# 15_ISP.net
KiCad netlist of a schematic drawn in Altium Designer
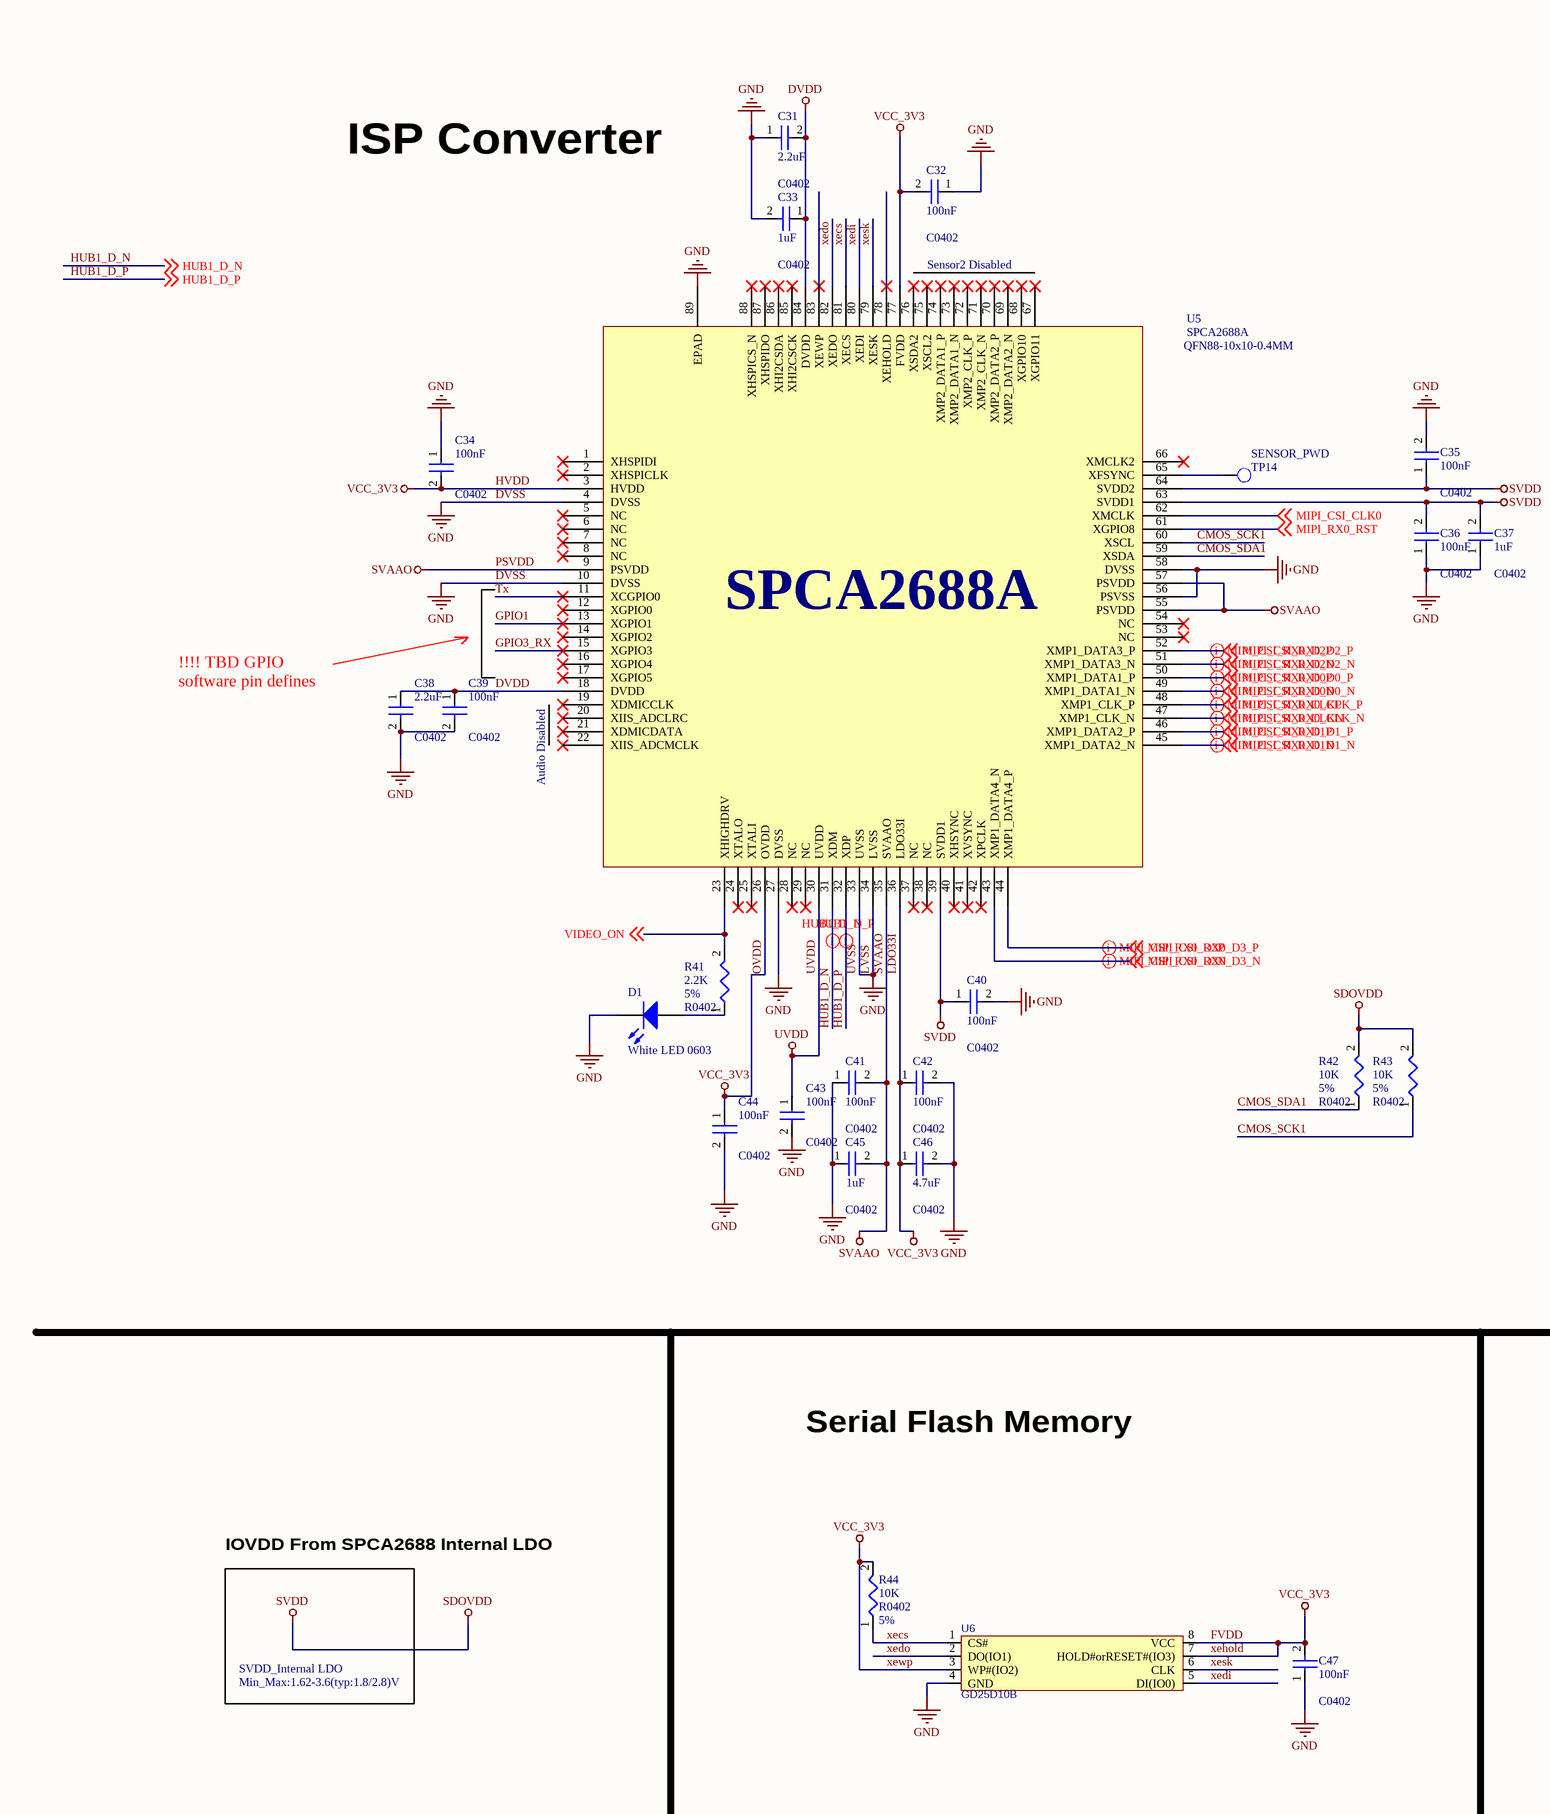
[diagram p0: 15_ISP.SchDoc, left]
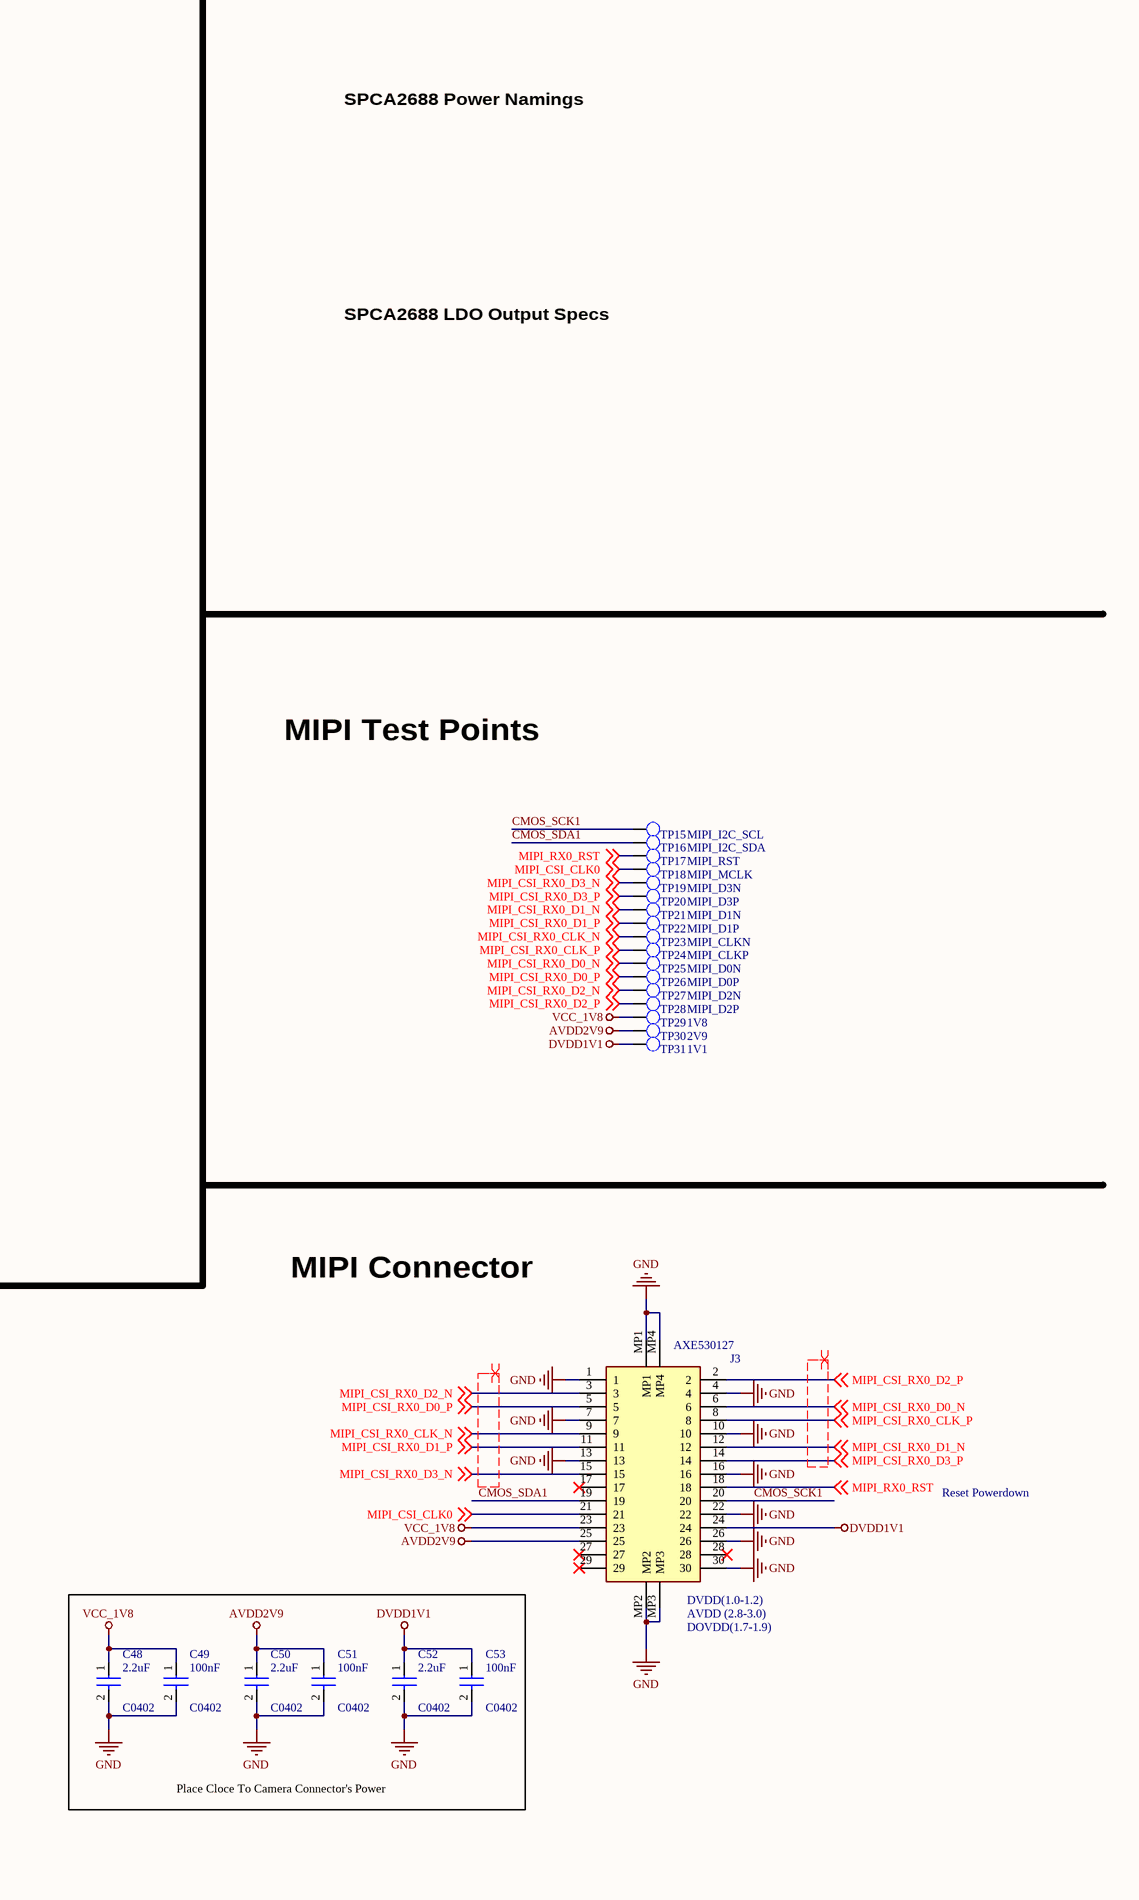
[diagram p1: 15_ISP.SchDoc, right]

(export (version "E")
  (design (tool "Eeschema 10.0.6"))
  (components
    (comp (ref "C31")
      (value "2.2uF")
      (footprint "C0402_L")
      (description "cap,2.20uF,+/-10%,10V,X5R,C0402")
      (fields (field (name "PCB FOOTPRINT") "C0402"))
      (libsource (lib "*") (part "CAP NP_Dup1"))
    )
    (comp (ref "C32")
      (value "100nF")
      (footprint "C0402_L")
      (description "cap,100.00nF,+/-10%,25V,X5R,C0402")
      (fields (field (name "PCB FOOTPRINT") "C0402"))
      (libsource (lib "*") (part "CAP NP_Dup1"))
    )
    (comp (ref "C33")
      (value "1uF")
      (footprint "C0402_L")
      (description "cap,1.00uF,+/-10%,6.3V,X5R,C0402")
      (fields (field (name "PCB FOOTPRINT") "C0402"))
      (libsource (lib "*") (part "CAP NP_Dup1"))
    )
    (comp (ref "C34")
      (value "100nF")
      (footprint "C0402_L")
      (description "cap,100.00nF,+/-10%,25V,X5R,C0402")
      (fields (field (name "PCB FOOTPRINT") "C0402"))
      (libsource (lib "*") (part "CAP NP_Dup1"))
    )
    (comp (ref "C35")
      (value "100nF")
      (footprint "C0402_L")
      (description "cap,100.00nF,+/-10%,25V,X5R,C0402")
      (fields (field (name "PCB FOOTPRINT") "C0402"))
      (libsource (lib "*") (part "CAP NP_Dup1"))
    )
    (comp (ref "C36")
      (value "100nF")
      (footprint "C0402_L")
      (description "cap,100.00nF,+/-10%,25V,X5R,C0402")
      (fields (field (name "PCB FOOTPRINT") "C0402"))
      (libsource (lib "*") (part "CAP NP_Dup1"))
    )
    (comp (ref "C37")
      (value "1uF")
      (footprint "C0402_L")
      (description "cap,1.00uF,+/-10%,6.3V,X5R,C0402")
      (fields (field (name "PCB FOOTPRINT") "C0402"))
      (libsource (lib "*") (part "CAP NP_Dup1"))
    )
    (comp (ref "C38")
      (value "2.2uF")
      (footprint "C0402_L")
      (description "cap,2.20uF,+/-10%,10V,X5R,C0402")
      (fields (field (name "PCB FOOTPRINT") "C0402"))
      (libsource (lib "*") (part "CAP NP_Dup1"))
    )
    (comp (ref "C39")
      (value "100nF")
      (footprint "C0402_L")
      (description "cap,100.00nF,+/-10%,25V,X5R,C0402")
      (fields (field (name "PCB FOOTPRINT") "C0402"))
      (libsource (lib "*") (part "CAP NP_Dup1"))
    )
    (comp (ref "C40")
      (value "100nF")
      (footprint "C0402_L")
      (description "cap,100.00nF,+/-10%,25V,X5R,C0402")
      (fields (field (name "PCB FOOTPRINT") "C0402"))
      (libsource (lib "*") (part "CAP NP_Dup1"))
    )
    (comp (ref "C41")
      (value "100nF")
      (footprint "C0402_L")
      (description "cap,100.00nF,+/-10%,25V,X5R,C0402")
      (fields (field (name "PCB FOOTPRINT") "C0402"))
      (libsource (lib "*") (part "CAP NP_Dup1"))
    )
    (comp (ref "C42")
      (value "100nF")
      (footprint "C0402_L")
      (description "cap,100.00nF,+/-10%,25V,X5R,C0402")
      (fields (field (name "PCB FOOTPRINT") "C0402"))
      (libsource (lib "*") (part "CAP NP_Dup1"))
    )
    (comp (ref "C43")
      (value "100nF")
      (footprint "C0402_L")
      (description "cap,100.00nF,+/-10%,25V,X5R,C0402")
      (fields (field (name "PCB FOOTPRINT") "C0402"))
      (libsource (lib "*") (part "CAP NP_Dup1"))
    )
    (comp (ref "C44")
      (value "100nF")
      (footprint "C0402_L")
      (description "cap,100.00nF,+/-10%,25V,X5R,C0402")
      (fields (field (name "PCB FOOTPRINT") "C0402"))
      (libsource (lib "*") (part "CAP NP_Dup1"))
    )
    (comp (ref "C45")
      (value "1uF")
      (footprint "C0402_L")
      (description "cap,1.00uF,+/-10%,10V,X5R,C0402")
      (fields (field (name "PCB FOOTPRINT") "C0402"))
      (libsource (lib "*") (part "CAP NP_Dup1"))
    )
    (comp (ref "C46")
      (value "4.7uF")
      (footprint "C0402_L")
      (description "cap,4.70uF,+/-10%,6.3V,X5R,C0402")
      (fields (field (name "PCB FOOTPRINT") "C0402"))
      (libsource (lib "*") (part "CAP NP_Dup1"))
    )
    (comp (ref "C47")
      (value "100nF")
      (footprint "C0402_L")
      (description "cap,100.00nF,+/-10%,25V,X5R,C0402")
      (fields (field (name "PCB FOOTPRINT") "C0402"))
      (libsource (lib "*") (part "CAP NP_Dup1"))
    )
    (comp (ref "C48")
      (value "2.2uF")
      (footprint "C0402_L")
      (description "cap,2.20uF,+/-10%,10V,X5R,C0402")
      (fields (field (name "PCB FOOTPRINT") "C0402"))
      (libsource (lib "*") (part "CAP NP_Dup1"))
    )
    (comp (ref "C49")
      (value "100nF")
      (footprint "C0402_L")
      (description "cap,100.00nF,+/-10%,25V,X5R,C0402")
      (fields (field (name "PCB FOOTPRINT") "C0402"))
      (libsource (lib "*") (part "CAP NP_Dup1"))
    )
    (comp (ref "C50")
      (value "2.2uF")
      (footprint "C0402_L")
      (description "cap,2.20uF,+/-10%,10V,X5R,C0402")
      (fields (field (name "PCB FOOTPRINT") "C0402"))
      (libsource (lib "*") (part "CAP NP_Dup1"))
    )
    (comp (ref "C51")
      (value "100nF")
      (footprint "C0402_L")
      (description "cap,100.00nF,+/-10%,25V,X5R,C0402")
      (fields (field (name "PCB FOOTPRINT") "C0402"))
      (libsource (lib "*") (part "CAP NP_Dup1"))
    )
    (comp (ref "C52")
      (value "2.2uF")
      (footprint "C0402_L")
      (description "cap,2.20uF,+/-10%,10V,X5R,C0402")
      (fields (field (name "PCB FOOTPRINT") "C0402"))
      (libsource (lib "*") (part "CAP NP_Dup1"))
    )
    (comp (ref "C53")
      (value "100nF")
      (footprint "C0402_L")
      (description "cap,100.00nF,+/-10%,25V,X5R,C0402")
      (fields (field (name "PCB FOOTPRINT") "C0402"))
      (libsource (lib "*") (part "CAP NP_Dup1"))
    )
    (comp (ref "D1")
      (value "White LED 0603")
      (footprint "LED0603_W")
      (description "LED 0603 Wite 发光二极管")
      (libsource (lib "0.3 - LED发光二极管-IR二极管_接收管-光耦") (part "LED"))
    )
    (comp (ref "J3")
      (value "AXE530127")
      (footprint "AXE530127_counterclock_pin")
      (description "AXE530127 Connector")
      (fields (field (name "MOUSER2 PART NUMBER") "679-AXE530127"))
      (libsource (lib "*") (part "AXE530127"))
    )
    (comp (ref "R41")
      (value "2.2K")
      (footprint "R0402")
      (description "通用厚膜电阻,2.2K,+/-5%,R0402")
      (fields (field (name "PCB FOOTPRINT") "R0402") (field (name "TOLERANCE") "5%"))
      (libsource (lib "*") (part "RESISTOR"))
    )
    (comp (ref "R42")
      (value "10K")
      (footprint "R0402")
      (description "通用厚膜电阻,10K,+/-5%,R0402")
      (fields (field (name "PCB FOOTPRINT") "R0402") (field (name "TOLERANCE") "5%"))
      (libsource (lib "*") (part "RESISTOR"))
    )
    (comp (ref "R43")
      (value "10K")
      (footprint "R0402")
      (description "通用厚膜电阻,10K,+/-5%,R0402")
      (fields (field (name "PCB FOOTPRINT") "R0402") (field (name "TOLERANCE") "5%"))
      (libsource (lib "*") (part "RESISTOR"))
    )
    (comp (ref "R44")
      (value "10K")
      (footprint "R0402")
      (description "通用厚膜电阻,10K,+/-5%,R0402")
      (fields (field (name "PCB FOOTPRINT") "R0402") (field (name "TOLERANCE") "5%"))
      (libsource (lib "*") (part "RESISTOR"))
    )
    (comp (ref "TP14")
      (value "SENSOR_PWD")
      (footprint "TP_0R70")
      (description "Test Point 0.7mm")
      (libsource (lib "Schlib1") (part "TP"))
    )
    (comp (ref "TP15")
      (value "MIPI_I2C_SCL")
      (footprint "TP_0R70")
      (description "Test Point 0.7mm")
      (libsource (lib "Schlib1") (part "TP"))
    )
    (comp (ref "TP16")
      (value "MIPI_I2C_SDA")
      (footprint "TP_0R70")
      (description "Test Point 0.7mm")
      (libsource (lib "Schlib1") (part "TP"))
    )
    (comp (ref "TP17")
      (value "MIPI_RST")
      (footprint "TP_0R70")
      (description "Test Point 0.7mm")
      (libsource (lib "Schlib1") (part "TP"))
    )
    (comp (ref "TP18")
      (value "MIPI_MCLK")
      (footprint "TP_0R70")
      (description "Test Point 0.7mm")
      (libsource (lib "Schlib1") (part "TP"))
    )
    (comp (ref "TP19")
      (value "MIPI_D3N")
      (footprint "TP_0R70")
      (description "Test Point 0.7mm")
      (libsource (lib "Schlib1") (part "TP"))
    )
    (comp (ref "TP20")
      (value "MIPI_D3P")
      (footprint "TP_0R70")
      (description "Test Point 0.7mm")
      (libsource (lib "Schlib1") (part "TP"))
    )
    (comp (ref "TP21")
      (value "MIPI_D1N")
      (footprint "TP_0R70")
      (description "Test Point 0.7mm")
      (libsource (lib "Schlib1") (part "TP"))
    )
    (comp (ref "TP22")
      (value "MIPI_D1P")
      (footprint "TP_0R70")
      (description "Test Point 0.7mm")
      (libsource (lib "Schlib1") (part "TP"))
    )
    (comp (ref "TP23")
      (value "MIPI_CLKN")
      (footprint "TP_0R70")
      (description "Test Point 0.7mm")
      (libsource (lib "Schlib1") (part "TP"))
    )
    (comp (ref "TP24")
      (value "MIPI_CLKP")
      (footprint "TP_0R70")
      (description "Test Point 0.7mm")
      (libsource (lib "Schlib1") (part "TP"))
    )
    (comp (ref "TP25")
      (value "MIPI_D0N")
      (footprint "TP_0R70")
      (description "Test Point 0.7mm")
      (libsource (lib "Schlib1") (part "TP"))
    )
    (comp (ref "TP26")
      (value "MIPI_D0P")
      (footprint "TP_0R70")
      (description "Test Point 0.7mm")
      (libsource (lib "Schlib1") (part "TP"))
    )
    (comp (ref "TP27")
      (value "MIPI_D2N")
      (footprint "TP_0R70")
      (description "Test Point 0.7mm")
      (libsource (lib "Schlib1") (part "TP"))
    )
    (comp (ref "TP28")
      (value "MIPI_D2P")
      (footprint "TP_0R70")
      (description "Test Point 0.7mm")
      (libsource (lib "Schlib1") (part "TP"))
    )
    (comp (ref "TP29")
      (value "1V8")
      (footprint "TP_0R70")
      (description "Test Point 0.7mm")
      (libsource (lib "Schlib1") (part "TP"))
    )
    (comp (ref "TP30")
      (value "2V9")
      (footprint "TP_0R70")
      (description "Test Point 0.7mm")
      (libsource (lib "Schlib1") (part "TP"))
    )
    (comp (ref "TP31")
      (value "1V1")
      (footprint "TP_0R70")
      (description "Test Point 0.7mm")
      (libsource (lib "Schlib1") (part "TP"))
    )
    (comp (ref "U5")
      (value "SPCA2688A")
      (footprint "QFN40P1000X1000X90-89N")
      (description "SPCA2688A ISP IC\r\nQFN88 10x10MM 0.4MM")
      (libsource (lib "Schlib1") (part "SPCA2688A"))
    )
    (comp (ref "U6")
      (value "GD25D10B")
      (footprint "SOIC-8")
      (description "SPI FLASH SOP-8")
      (libsource (lib "Schlib1") (part "GD25D10B"))
    )
  )
  (nets
    (net (code "1") (name "/CMOS_SCK1") (class "Default")
      (node (ref "J3") (pin "20") (pinfunction "20_20") (pintype "passive"))
      (node (ref "R43") (pin "1") (pinfunction "1_1") (pintype "passive"))
      (node (ref "TP15") (pin "1") (pinfunction "1_1") (pintype "passive"))
      (node (ref "U5") (pin "60") (pinfunction "XSCL_60") (pintype "passive"))
    )
    (net (code "2") (name "/CMOS_SDA1") (class "Default")
      (node (ref "J3") (pin "19") (pinfunction "19_19") (pintype "passive"))
      (node (ref "R42") (pin "1") (pinfunction "1_1") (pintype "passive"))
      (node (ref "TP16") (pin "1") (pinfunction "1_1") (pintype "passive"))
      (node (ref "U5") (pin "59") (pinfunction "XSDA_59") (pintype "passive"))
    )
    (net (code "3") (name "/GPIO1") (class "Default")
      (node (ref "U5") (pin "13") (pinfunction "XGPIO1_13") (pintype "passive+no_connect"))
    )
    (net (code "4") (name "/GPIO3_RX") (class "Default")
      (node (ref "U5") (pin "15") (pinfunction "XGPIO3_15") (pintype "passive+no_connect"))
    )
    (net (code "5") (name "/Tx") (class "Default")
      (node (ref "U5") (pin "11") (pinfunction "XCGPIO0_11") (pintype "passive+no_connect"))
    )
    (net (code "6") (name "/xecs") (class "Default")
      (node (ref "R44") (pin "1") (pinfunction "1_1") (pintype "passive"))
      (node (ref "U5") (pin "81") (pinfunction "XECS_81") (pintype "passive"))
      (node (ref "U6") (pin "1") (pinfunction "CS#_1") (pintype "passive"))
    )
    (net (code "7") (name "/xedi") (class "Default")
      (node (ref "U5") (pin "80") (pinfunction "XEDI_80") (pintype "passive"))
      (node (ref "U6") (pin "5") (pinfunction "DI(IO0)_5") (pintype "passive"))
    )
    (net (code "8") (name "/xedo") (class "Default")
      (node (ref "U5") (pin "82") (pinfunction "XEDO_82") (pintype "passive"))
      (node (ref "U6") (pin "2") (pinfunction "DO(IO1)_2") (pintype "passive"))
    )
    (net (code "9") (name "/xesk") (class "Default")
      (node (ref "U5") (pin "79") (pinfunction "XESK_79") (pintype "passive"))
      (node (ref "U6") (pin "6") (pinfunction "CLK_6") (pintype "passive"))
    )
    (net (code "10") (name "AVDD2V9") (class "Default")
      (node (ref "C50") (pin "1") (pinfunction "1_1") (pintype "passive"))
      (node (ref "C51") (pin "1") (pinfunction "1_1") (pintype "passive"))
      (node (ref "J3") (pin "25") (pinfunction "25_25") (pintype "passive"))
      (node (ref "TP30") (pin "1") (pinfunction "1_1") (pintype "passive"))
    )
    (net (code "11") (name "DVDD") (class "Default")
      (node (ref "C31") (pin "2") (pinfunction "2_2") (pintype "passive"))
      (node (ref "C33") (pin "1") (pinfunction "1_1") (pintype "passive"))
      (node (ref "C38") (pin "1") (pinfunction "1_1") (pintype "passive"))
      (node (ref "C39") (pin "1") (pinfunction "1_1") (pintype "passive"))
      (node (ref "U5") (pin "18") (pinfunction "DVDD_18") (pintype "passive"))
      (node (ref "U5") (pin "84") (pinfunction "DVDD_84") (pintype "passive"))
    )
    (net (code "12") (name "DVDD1V1") (class "Default")
      (node (ref "C52") (pin "1") (pinfunction "1_1") (pintype "passive"))
      (node (ref "C53") (pin "1") (pinfunction "1_1") (pintype "passive"))
      (node (ref "J3") (pin "24") (pinfunction "24_24") (pintype "passive"))
      (node (ref "TP31") (pin "1") (pinfunction "1_1") (pintype "passive"))
    )
    (net (code "13") (name "GND") (class "Default")
      (node (ref "C31") (pin "1") (pinfunction "1_1") (pintype "passive"))
      (node (ref "C32") (pin "1") (pinfunction "1_1") (pintype "passive"))
      (node (ref "C33") (pin "2") (pinfunction "2_2") (pintype "passive"))
      (node (ref "C34") (pin "1") (pinfunction "1_1") (pintype "passive"))
      (node (ref "C35") (pin "2") (pinfunction "2_2") (pintype "passive"))
      (node (ref "C36") (pin "1") (pinfunction "1_1") (pintype "passive"))
      (node (ref "C37") (pin "1") (pinfunction "1_1") (pintype "passive"))
      (node (ref "C38") (pin "2") (pinfunction "2_2") (pintype "passive"))
      (node (ref "C39") (pin "2") (pinfunction "2_2") (pintype "passive"))
      (node (ref "C40") (pin "2") (pinfunction "2_2") (pintype "passive"))
      (node (ref "C41") (pin "1") (pinfunction "1_1") (pintype "passive"))
      (node (ref "C42") (pin "2") (pinfunction "2_2") (pintype "passive"))
      (node (ref "C43") (pin "2") (pinfunction "2_2") (pintype "passive"))
      (node (ref "C44") (pin "2") (pinfunction "2_2") (pintype "passive"))
      (node (ref "C45") (pin "1") (pinfunction "1_1") (pintype "passive"))
      (node (ref "C46") (pin "2") (pinfunction "2_2") (pintype "passive"))
      (node (ref "C47") (pin "1") (pinfunction "1_1") (pintype "passive"))
      (node (ref "C48") (pin "2") (pinfunction "2_2") (pintype "passive"))
      (node (ref "C49") (pin "2") (pinfunction "2_2") (pintype "passive"))
      (node (ref "C50") (pin "2") (pinfunction "2_2") (pintype "passive"))
      (node (ref "C51") (pin "2") (pinfunction "2_2") (pintype "passive"))
      (node (ref "C52") (pin "2") (pinfunction "2_2") (pintype "passive"))
      (node (ref "C53") (pin "2") (pinfunction "2_2") (pintype "passive"))
      (node (ref "D1") (pin "2") (pinfunction "K_2") (pintype "passive"))
      (node (ref "J3") (pin "1") (pinfunction "1_1") (pintype "passive"))
      (node (ref "J3") (pin "10") (pinfunction "10_10") (pintype "passive"))
      (node (ref "J3") (pin "13") (pinfunction "13_13") (pintype "passive"))
      (node (ref "J3") (pin "16") (pinfunction "16_16") (pintype "passive"))
      (node (ref "J3") (pin "22") (pinfunction "22_22") (pintype "passive"))
      (node (ref "J3") (pin "26") (pinfunction "26_26") (pintype "passive"))
      (node (ref "J3") (pin "30") (pinfunction "30_30") (pintype "passive"))
      (node (ref "J3") (pin "4") (pinfunction "4_4") (pintype "passive"))
      (node (ref "J3") (pin "7") (pinfunction "7_7") (pintype "passive"))
      (node (ref "J3") (pin "MP1") (pinfunction "MP1_MP1") (pintype "passive"))
      (node (ref "J3") (pin "MP2") (pinfunction "MP2_MP2") (pintype "passive"))
      (node (ref "J3") (pin "MP3") (pinfunction "MP3_MP3") (pintype "passive"))
      (node (ref "J3") (pin "MP4") (pinfunction "MP4_MP4") (pintype "passive"))
      (node (ref "U5") (pin "10") (pinfunction "DVSS_10") (pintype "passive"))
      (node (ref "U5") (pin "27") (pinfunction "DVSS_27") (pintype "passive"))
      (node (ref "U5") (pin "33") (pinfunction "UVSS_33") (pintype "passive"))
      (node (ref "U5") (pin "34") (pinfunction "LVSS_34") (pintype "passive"))
      (node (ref "U5") (pin "4") (pinfunction "DVSS_4") (pintype "passive"))
      (node (ref "U5") (pin "56") (pinfunction "PSVSS_56") (pintype "passive"))
      (node (ref "U5") (pin "58") (pinfunction "DVSS_58") (pintype "passive"))
      (node (ref "U5") (pin "89") (pinfunction "EPAD_89") (pintype "passive"))
      (node (ref "U6") (pin "4") (pinfunction "GND_4") (pintype "passive"))
    )
    (net (code "14") (name "HUB1_D_N") (class "Default")
      (node (ref "U5") (pin "31") (pinfunction "XDM_31") (pintype "passive"))
    )
    (net (code "15") (name "HUB1_D_P") (class "Default")
      (node (ref "U5") (pin "32") (pinfunction "XDP_32") (pintype "passive"))
    )
    (net (code "16") (name "MIPI_CSI_CLK0") (class "Default")
      (node (ref "J3") (pin "21") (pinfunction "21_21") (pintype "passive"))
      (node (ref "TP18") (pin "1") (pinfunction "1_1") (pintype "passive"))
      (node (ref "U5") (pin "62") (pinfunction "XMCLK_62") (pintype "passive"))
    )
    (net (code "17") (name "MIPI_CSI_RX0_CLK_N") (class "Default")
      (node (ref "J3") (pin "9") (pinfunction "9_9") (pintype "passive"))
      (node (ref "TP23") (pin "1") (pinfunction "1_1") (pintype "passive"))
      (node (ref "U5") (pin "47") (pinfunction "XMP1_CLK_N_47") (pintype "passive"))
    )
    (net (code "18") (name "MIPI_CSI_RX0_CLK_P") (class "Default")
      (node (ref "J3") (pin "8") (pinfunction "8_8") (pintype "passive"))
      (node (ref "TP24") (pin "1") (pinfunction "1_1") (pintype "passive"))
      (node (ref "U5") (pin "48") (pinfunction "XMP1_CLK_P_48") (pintype "passive"))
    )
    (net (code "19") (name "MIPI_CSI_RX0_D0_N") (class "Default")
      (node (ref "J3") (pin "6") (pinfunction "6_6") (pintype "passive"))
      (node (ref "TP25") (pin "1") (pinfunction "1_1") (pintype "passive"))
      (node (ref "U5") (pin "49") (pinfunction "XMP1_DATA1_N_49") (pintype "passive"))
    )
    (net (code "20") (name "MIPI_CSI_RX0_D0_P") (class "Default")
      (node (ref "J3") (pin "5") (pinfunction "5_5") (pintype "passive"))
      (node (ref "TP26") (pin "1") (pinfunction "1_1") (pintype "passive"))
      (node (ref "U5") (pin "50") (pinfunction "XMP1_DATA1_P_50") (pintype "passive"))
    )
    (net (code "21") (name "MIPI_CSI_RX0_D1_N") (class "Default")
      (node (ref "J3") (pin "12") (pinfunction "12_12") (pintype "passive"))
      (node (ref "TP21") (pin "1") (pinfunction "1_1") (pintype "passive"))
      (node (ref "U5") (pin "45") (pinfunction "XMP1_DATA2_N_45") (pintype "passive"))
    )
    (net (code "22") (name "MIPI_CSI_RX0_D1_P") (class "Default")
      (node (ref "J3") (pin "11") (pinfunction "11_11") (pintype "passive"))
      (node (ref "TP22") (pin "1") (pinfunction "1_1") (pintype "passive"))
      (node (ref "U5") (pin "46") (pinfunction "XMP1_DATA2_P_46") (pintype "passive"))
    )
    (net (code "23") (name "MIPI_CSI_RX0_D2_N") (class "Default")
      (node (ref "J3") (pin "3") (pinfunction "3_3") (pintype "passive"))
      (node (ref "TP27") (pin "1") (pinfunction "1_1") (pintype "passive"))
      (node (ref "U5") (pin "51") (pinfunction "XMP1_DATA3_N_51") (pintype "passive"))
    )
    (net (code "24") (name "MIPI_CSI_RX0_D2_P") (class "Default")
      (node (ref "J3") (pin "2") (pinfunction "2_2") (pintype "passive"))
      (node (ref "TP28") (pin "1") (pinfunction "1_1") (pintype "passive"))
      (node (ref "U5") (pin "52") (pinfunction "XMP1_DATA3_P_52") (pintype "passive"))
    )
    (net (code "25") (name "MIPI_CSI_RX0_D3_N") (class "Default")
      (node (ref "J3") (pin "15") (pinfunction "15_15") (pintype "passive"))
      (node (ref "TP19") (pin "1") (pinfunction "1_1") (pintype "passive"))
      (node (ref "U5") (pin "43") (pinfunction "XMP1_DATA4_N_43") (pintype "passive"))
    )
    (net (code "26") (name "MIPI_CSI_RX0_D3_P") (class "Default")
      (node (ref "J3") (pin "14") (pinfunction "14_14") (pintype "passive"))
      (node (ref "TP20") (pin "1") (pinfunction "1_1") (pintype "passive"))
      (node (ref "U5") (pin "44") (pinfunction "XMP1_DATA4_P_44") (pintype "passive"))
    )
    (net (code "27") (name "MIPI_RX0_RST") (class "Default")
      (node (ref "J3") (pin "18") (pinfunction "18_18") (pintype "passive"))
      (node (ref "TP17") (pin "1") (pinfunction "1_1") (pintype "passive"))
      (node (ref "U5") (pin "61") (pinfunction "XGPIO8_61") (pintype "passive"))
    )
    (net (code "28") (name "Net-(D1-A)") (class "Default")
      (node (ref "D1") (pin "1") (pinfunction "A_1") (pintype "passive"))
      (node (ref "R41") (pin "1") (pinfunction "1_1") (pintype "passive"))
    )
    (net (code "29") (name "Net-(U5-XFSYNC)") (class "Default")
      (node (ref "TP14") (pin "1") (pinfunction "1_1") (pintype "passive"))
      (node (ref "U5") (pin "65") (pinfunction "XFSYNC_65") (pintype "passive"))
    )
    (net (code "30") (name "SDOVDD") (class "Default")
      (node (ref "C35") (pin "1") (pinfunction "1_1") (pintype "passive"))
      (node (ref "C36") (pin "2") (pinfunction "2_2") (pintype "passive"))
      (node (ref "C37") (pin "2") (pinfunction "2_2") (pintype "passive"))
      (node (ref "C40") (pin "1") (pinfunction "1_1") (pintype "passive"))
      (node (ref "R42") (pin "2") (pinfunction "2_2") (pintype "passive"))
      (node (ref "R43") (pin "2") (pinfunction "2_2") (pintype "passive"))
      (node (ref "U5") (pin "39") (pinfunction "SVDD1_39") (pintype "passive"))
      (node (ref "U5") (pin "63") (pinfunction "SVDD1_63") (pintype "passive"))
      (node (ref "U5") (pin "64") (pinfunction "SVDD2_64") (pintype "passive"))
    )
    (net (code "31") (name "SVAAO") (class "Default")
      (node (ref "C41") (pin "2") (pinfunction "2_2") (pintype "passive"))
      (node (ref "C45") (pin "2") (pinfunction "2_2") (pintype "passive"))
      (node (ref "U5") (pin "35") (pinfunction "SVAAO_35") (pintype "passive"))
      (node (ref "U5") (pin "55") (pinfunction "PSVDD_55") (pintype "passive"))
      (node (ref "U5") (pin "57") (pinfunction "PSVDD_57") (pintype "passive"))
      (node (ref "U5") (pin "9") (pinfunction "PSVDD_9") (pintype "passive"))
    )
    (net (code "32") (name "UVDD") (class "Default")
      (node (ref "C43") (pin "1") (pinfunction "1_1") (pintype "passive"))
      (node (ref "U5") (pin "30") (pinfunction "UVDD_30") (pintype "passive"))
    )
    (net (code "33") (name "VCC_1V8") (class "Default")
      (node (ref "C48") (pin "1") (pinfunction "1_1") (pintype "passive"))
      (node (ref "C49") (pin "1") (pinfunction "1_1") (pintype "passive"))
      (node (ref "J3") (pin "23") (pinfunction "23_23") (pintype "passive"))
      (node (ref "TP29") (pin "1") (pinfunction "1_1") (pintype "passive"))
    )
    (net (code "34") (name "VCC_3V3") (class "Default")
      (node (ref "C32") (pin "2") (pinfunction "2_2") (pintype "passive"))
      (node (ref "C34") (pin "2") (pinfunction "2_2") (pintype "passive"))
      (node (ref "C42") (pin "1") (pinfunction "1_1") (pintype "passive"))
      (node (ref "C44") (pin "1") (pinfunction "1_1") (pintype "passive"))
      (node (ref "C46") (pin "1") (pinfunction "1_1") (pintype "passive"))
      (node (ref "C47") (pin "2") (pinfunction "2_2") (pintype "passive"))
      (node (ref "R44") (pin "2") (pinfunction "2_2") (pintype "passive"))
      (node (ref "U5") (pin "26") (pinfunction "OVDD_26") (pintype "passive"))
      (node (ref "U5") (pin "3") (pinfunction "HVDD_3") (pintype "passive"))
      (node (ref "U5") (pin "36") (pinfunction "LDO33I_36") (pintype "passive"))
      (node (ref "U5") (pin "77") (pinfunction "FVDD_77") (pintype "passive"))
      (node (ref "U6") (pin "3") (pinfunction "WP#(IO2)_3") (pintype "passive"))
      (node (ref "U6") (pin "7") (pinfunction "HOLD#orRESET#(IO3)_7") (pintype "passive"))
      (node (ref "U6") (pin "8") (pinfunction "VCC_8") (pintype "passive"))
    )
    (net (code "35") (name "VIDEO_ON") (class "Default")
      (node (ref "R41") (pin "2") (pinfunction "2_2") (pintype "passive"))
      (node (ref "U5") (pin "23") (pinfunction "XHIGHDRV_23") (pintype "passive"))
    )
    (net (code "36") (name "unconnected-(J3-Pad17)") (class "Default")
      (node (ref "J3") (pin "17") (pinfunction "17_17") (pintype "passive+no_connect"))
    )
    (net (code "37") (name "unconnected-(J3-Pad27)") (class "Default")
      (node (ref "J3") (pin "27") (pinfunction "27_27") (pintype "passive+no_connect"))
    )
    (net (code "38") (name "unconnected-(J3-Pad28)") (class "Default")
      (node (ref "J3") (pin "28") (pinfunction "28_28") (pintype "passive+no_connect"))
    )
    (net (code "39") (name "unconnected-(J3-Pad29)") (class "Default")
      (node (ref "J3") (pin "29") (pinfunction "29_29") (pintype "passive+no_connect"))
    )
    (net (code "40") (name "unconnected-(U5-NC-Pad5)") (class "Default")
      (node (ref "U5") (pin "5") (pinfunction "NC_5") (pintype "passive+no_connect"))
    )
    (net (code "41") (name "unconnected-(U5-NC-Pad6)") (class "Default")
      (node (ref "U5") (pin "6") (pinfunction "NC_6") (pintype "passive+no_connect"))
    )
    (net (code "42") (name "unconnected-(U5-NC-Pad7)") (class "Default")
      (node (ref "U5") (pin "7") (pinfunction "NC_7") (pintype "passive+no_connect"))
    )
    (net (code "43") (name "unconnected-(U5-NC-Pad8)") (class "Default")
      (node (ref "U5") (pin "8") (pinfunction "NC_8") (pintype "passive+no_connect"))
    )
    (net (code "44") (name "unconnected-(U5-NC-Pad28)") (class "Default")
      (node (ref "U5") (pin "28") (pinfunction "NC_28") (pintype "passive+no_connect"))
    )
    (net (code "45") (name "unconnected-(U5-NC-Pad29)") (class "Default")
      (node (ref "U5") (pin "29") (pinfunction "NC_29") (pintype "passive+no_connect"))
    )
    (net (code "46") (name "unconnected-(U5-NC-Pad37)") (class "Default")
      (node (ref "U5") (pin "37") (pinfunction "NC_37") (pintype "passive+no_connect"))
    )
    (net (code "47") (name "unconnected-(U5-NC-Pad38)") (class "Default")
      (node (ref "U5") (pin "38") (pinfunction "NC_38") (pintype "passive+no_connect"))
    )
    (net (code "48") (name "unconnected-(U5-NC-Pad53)") (class "Default")
      (node (ref "U5") (pin "53") (pinfunction "NC_53") (pintype "passive+no_connect"))
    )
    (net (code "49") (name "unconnected-(U5-NC-Pad54)") (class "Default")
      (node (ref "U5") (pin "54") (pinfunction "NC_54") (pintype "passive+no_connect"))
    )
    (net (code "50") (name "unconnected-(U5-XDMICCLK-Pad19)") (class "Default")
      (node (ref "U5") (pin "19") (pinfunction "XDMICCLK_19") (pintype "passive+no_connect"))
    )
    (net (code "51") (name "unconnected-(U5-XDMICDATA-Pad21)") (class "Default")
      (node (ref "U5") (pin "21") (pinfunction "XDMICDATA_21") (pintype "passive+no_connect"))
    )
    (net (code "52") (name "unconnected-(U5-XEHOLD-Pad78)") (class "Default")
      (node (ref "U5") (pin "78") (pinfunction "XEHOLD_78") (pintype "passive+no_connect"))
    )
    (net (code "53") (name "unconnected-(U5-XEWP-Pad83)") (class "Default")
      (node (ref "U5") (pin "83") (pinfunction "XEWP_83") (pintype "passive+no_connect"))
    )
    (net (code "54") (name "unconnected-(U5-XGPIO0-Pad12)") (class "Default")
      (node (ref "U5") (pin "12") (pinfunction "XGPIO0_12") (pintype "passive+no_connect"))
    )
    (net (code "55") (name "unconnected-(U5-XGPIO2-Pad14)") (class "Default")
      (node (ref "U5") (pin "14") (pinfunction "XGPIO2_14") (pintype "passive+no_connect"))
    )
    (net (code "56") (name "unconnected-(U5-XGPIO4-Pad16)") (class "Default")
      (node (ref "U5") (pin "16") (pinfunction "XGPIO4_16") (pintype "passive+no_connect"))
    )
    (net (code "57") (name "unconnected-(U5-XGPIO5-Pad17)") (class "Default")
      (node (ref "U5") (pin "17") (pinfunction "XGPIO5_17") (pintype "passive+no_connect"))
    )
    (net (code "58") (name "unconnected-(U5-XGPIO10-Pad68)") (class "Default")
      (node (ref "U5") (pin "68") (pinfunction "XGPIO10_68") (pintype "passive+no_connect"))
    )
    (net (code "59") (name "unconnected-(U5-XGPIO11-Pad67)") (class "Default")
      (node (ref "U5") (pin "67") (pinfunction "XGPIO11_67") (pintype "passive+no_connect"))
    )
    (net (code "60") (name "unconnected-(U5-XHI2CSCK-Pad85)") (class "Default")
      (node (ref "U5") (pin "85") (pinfunction "XHI2CSCK_85") (pintype "passive+no_connect"))
    )
    (net (code "61") (name "unconnected-(U5-XHI2CSDA-Pad86)") (class "Default")
      (node (ref "U5") (pin "86") (pinfunction "XHI2CSDA_86") (pintype "passive+no_connect"))
    )
    (net (code "62") (name "unconnected-(U5-XHSPICLK-Pad2)") (class "Default")
      (node (ref "U5") (pin "2") (pinfunction "XHSPICLK_2") (pintype "passive+no_connect"))
    )
    (net (code "63") (name "unconnected-(U5-XHSPICS_N-Pad88)") (class "Default")
      (node (ref "U5") (pin "88") (pinfunction "XHSPICS_N_88") (pintype "passive+no_connect"))
    )
    (net (code "64") (name "unconnected-(U5-XHSPIDI-Pad1)") (class "Default")
      (node (ref "U5") (pin "1") (pinfunction "XHSPIDI_1") (pintype "passive+no_connect"))
    )
    (net (code "65") (name "unconnected-(U5-XHSPIDO-Pad87)") (class "Default")
      (node (ref "U5") (pin "87") (pinfunction "XHSPIDO_87") (pintype "passive+no_connect"))
    )
    (net (code "66") (name "unconnected-(U5-XHSYNC-Pad40)") (class "Default")
      (node (ref "U5") (pin "40") (pinfunction "XHSYNC_40") (pintype "passive+no_connect"))
    )
    (net (code "67") (name "unconnected-(U5-XIIS_ADCLRC-Pad20)") (class "Default")
      (node (ref "U5") (pin "20") (pinfunction "XIIS_ADCLRC_20") (pintype "passive+no_connect"))
    )
    (net (code "68") (name "unconnected-(U5-XIIS_ADCMCLK-Pad22)") (class "Default")
      (node (ref "U5") (pin "22") (pinfunction "XIIS_ADCMCLK_22") (pintype "passive+no_connect"))
    )
    (net (code "69") (name "unconnected-(U5-XMCLK2-Pad66)") (class "Default")
      (node (ref "U5") (pin "66") (pinfunction "XMCLK2_66") (pintype "passive+no_connect"))
    )
    (net (code "70") (name "unconnected-(U5-XMP2_CLK_N-Pad71)") (class "Default")
      (node (ref "U5") (pin "71") (pinfunction "XMP2_CLK_N_71") (pintype "passive+no_connect"))
    )
    (net (code "71") (name "unconnected-(U5-XMP2_CLK_P-Pad72)") (class "Default")
      (node (ref "U5") (pin "72") (pinfunction "XMP2_CLK_P_72") (pintype "passive+no_connect"))
    )
    (net (code "72") (name "unconnected-(U5-XMP2_DATA1_N-Pad73)") (class "Default")
      (node (ref "U5") (pin "73") (pinfunction "XMP2_DATA1_N_73") (pintype "passive+no_connect"))
    )
    (net (code "73") (name "unconnected-(U5-XMP2_DATA1_P-Pad74)") (class "Default")
      (node (ref "U5") (pin "74") (pinfunction "XMP2_DATA1_P_74") (pintype "passive+no_connect"))
    )
    (net (code "74") (name "unconnected-(U5-XMP2_DATA2_N-Pad69)") (class "Default")
      (node (ref "U5") (pin "69") (pinfunction "XMP2_DATA2_N_69") (pintype "passive+no_connect"))
    )
    (net (code "75") (name "unconnected-(U5-XMP2_DATA2_P-Pad70)") (class "Default")
      (node (ref "U5") (pin "70") (pinfunction "XMP2_DATA2_P_70") (pintype "passive+no_connect"))
    )
    (net (code "76") (name "unconnected-(U5-XPCLK-Pad42)") (class "Default")
      (node (ref "U5") (pin "42") (pinfunction "XPCLK_42") (pintype "passive+no_connect"))
    )
    (net (code "77") (name "unconnected-(U5-XSCL2-Pad75)") (class "Default")
      (node (ref "U5") (pin "75") (pinfunction "XSCL2_75") (pintype "passive+no_connect"))
    )
    (net (code "78") (name "unconnected-(U5-XSDA2-Pad76)") (class "Default")
      (node (ref "U5") (pin "76") (pinfunction "XSDA2_76") (pintype "passive+no_connect"))
    )
    (net (code "79") (name "unconnected-(U5-XTALI-Pad25)") (class "Default")
      (node (ref "U5") (pin "25") (pinfunction "XTALI_25") (pintype "passive+no_connect"))
    )
    (net (code "80") (name "unconnected-(U5-XTALO-Pad24)") (class "Default")
      (node (ref "U5") (pin "24") (pinfunction "XTALO_24") (pintype "passive+no_connect"))
    )
    (net (code "81") (name "unconnected-(U5-XVSYNC-Pad41)") (class "Default")
      (node (ref "U5") (pin "41") (pinfunction "XVSYNC_41") (pintype "passive+no_connect"))
    )
  )
)
